# Sheet1_TRP.net
KiCad netlist of a schematic drawn in Altium Designer
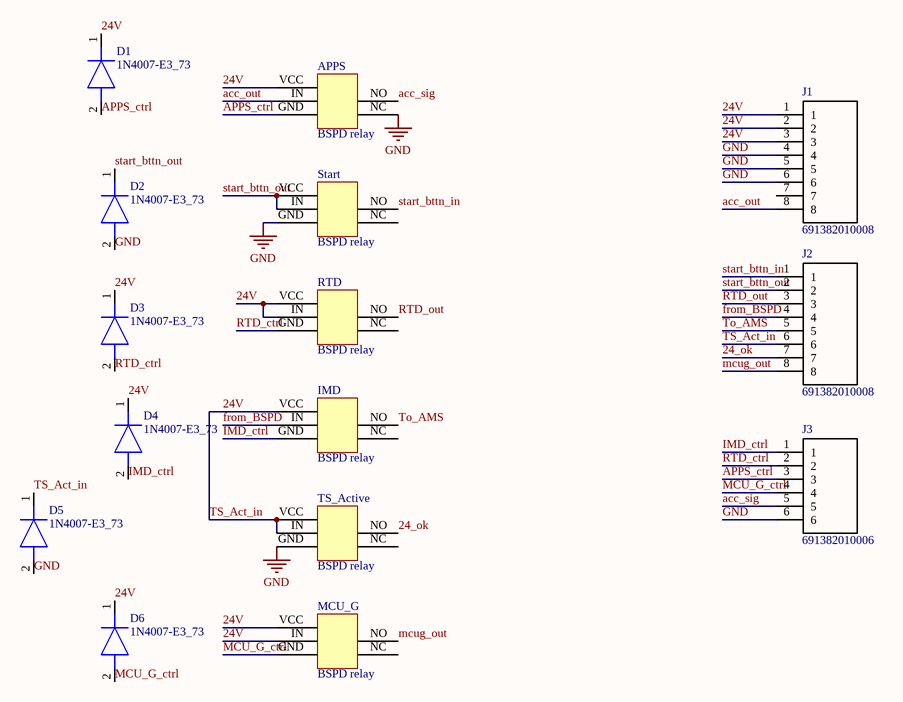
[diagram p0: Sheet1_TRP.SchDoc]

(export (version "E")
  (design (tool "Eeschema 10.0.6"))
  (components
    (comp (ref "APPS")
      (value "BSPD relay")
      (footprint "relay")
      (libsource (lib "Schlib1_TRP") (part "leone_relay"))
    )
    (comp (ref "D1")
      (value "1N4007-E3_73")
      (footprint "PcbLib1_TRP:DIOAD1405W86L465D235")
      (description "Diode")
      (fields
        (field (name "MANUFACTURER_PART_NUMBER") "1N4007-E3/73")
        (field (name "MOUSER PART NUMBER") "625-1N4007-E3/73")
      )
      (libsource (lib "*") (part "1N4007-E3_73"))
    )
    (comp (ref "D2")
      (value "1N4007-E3_73")
      (footprint "PcbLib1_TRP:DIOAD1405W86L465D235")
      (description "Diode")
      (fields
        (field (name "MANUFACTURER_PART_NUMBER") "1N4007-E3/73")
        (field (name "MOUSER PART NUMBER") "625-1N4007-E3/73")
      )
      (libsource (lib "*") (part "1N4007-E3_73"))
    )
    (comp (ref "D3")
      (value "1N4007-E3_73")
      (footprint "PcbLib1_TRP:DIOAD1405W86L465D235")
      (description "Diode")
      (fields
        (field (name "MANUFACTURER_PART_NUMBER") "1N4007-E3/73")
        (field (name "MOUSER PART NUMBER") "625-1N4007-E3/73")
      )
      (libsource (lib "*") (part "1N4007-E3_73"))
    )
    (comp (ref "D4")
      (value "1N4007-E3_73")
      (footprint "PcbLib1_TRP:DIOAD1405W86L465D235")
      (description "Diode")
      (fields
        (field (name "MANUFACTURER_PART_NUMBER") "1N4007-E3/73")
        (field (name "MOUSER PART NUMBER") "625-1N4007-E3/73")
      )
      (libsource (lib "*") (part "1N4007-E3_73"))
    )
    (comp (ref "D5")
      (value "1N4007-E3_73")
      (footprint "PcbLib1_TRP:DIOAD1405W86L465D235")
      (description "Diode")
      (fields
        (field (name "MANUFACTURER_PART_NUMBER") "1N4007-E3/73")
        (field (name "MOUSER PART NUMBER") "625-1N4007-E3/73")
      )
      (libsource (lib "*") (part "1N4007-E3_73"))
    )
    (comp (ref "D6")
      (value "1N4007-E3_73")
      (footprint "PcbLib1_TRP:DIOAD1405W86L465D235")
      (description "Diode")
      (fields
        (field (name "MANUFACTURER_PART_NUMBER") "1N4007-E3/73")
        (field (name "MOUSER PART NUMBER") "625-1N4007-E3/73")
      )
      (libsource (lib "*") (part "1N4007-E3_73"))
    )
    (comp (ref "IMD")
      (value "BSPD relay")
      (footprint "relay")
      (libsource (lib "Schlib1_TRP") (part "leone_relay"))
    )
    (comp (ref "J1")
      (value "691382010008")
      (footprint "PcbLib1_TRP:SHDRRA8W80P0X250_1X8_2200X1010X830P")
      (description "Connector")
      (fields (field (name "MOUSER PART NUMBER") "710-691382010008"))
      (libsource (lib "Schlib1_TRP") (part "691382010008"))
    )
    (comp (ref "J2")
      (value "691382010008")
      (footprint "PcbLib1_TRP:SHDRRA8W80P0X250_1X8_2200X1010X830P")
      (description "Connector")
      (fields (field (name "MOUSER PART NUMBER") "710-691382010008"))
      (libsource (lib "Schlib1_TRP") (part "691382010008"))
    )
    (comp (ref "J3")
      (value "691382010006")
      (footprint "PcbLib1_TRP:SHDRRA6W100P0X250_1X6_1700X1010X830P")
      (description "Connector")
      (fields (field (name "MOUSER PART NUMBER") "710-691382010006"))
      (libsource (lib "*") (part "691382010006"))
    )
    (comp (ref "MCU_G")
      (value "BSPD relay")
      (footprint "relay")
      (libsource (lib "Schlib1_TRP") (part "leone_relay"))
    )
    (comp (ref "RTD")
      (value "BSPD relay")
      (footprint "relay")
      (libsource (lib "Schlib1_TRP") (part "leone_relay"))
    )
    (comp (ref "Start")
      (value "BSPD relay")
      (footprint "relay")
      (libsource (lib "Schlib1_TRP") (part "leone_relay"))
    )
    (comp (ref "TS_Active")
      (value "BSPD relay")
      (footprint "relay")
      (libsource (lib "Schlib1_TRP") (part "leone_relay"))
    )
  )
  (nets
    (net (code "1") (name "/24V") (class "Default")
      (node (ref "APPS") (pin "VCC") (pintype "passive"))
      (node (ref "D1") (pin "1") (pinfunction "K_1") (pintype "passive"))
      (node (ref "D3") (pin "1") (pinfunction "K_1") (pintype "passive"))
      (node (ref "D4") (pin "1") (pinfunction "K_1") (pintype "passive"))
      (node (ref "D5") (pin "1") (pinfunction "K_1") (pintype "passive"))
      (node (ref "D6") (pin "1") (pinfunction "K_1") (pintype "passive"))
      (node (ref "IMD") (pin "VCC") (pintype "passive"))
      (node (ref "J1") (pin "1") (pinfunction "1_1") (pintype "passive"))
      (node (ref "J1") (pin "2") (pinfunction "2_2") (pintype "passive"))
      (node (ref "J1") (pin "3") (pinfunction "3_3") (pintype "passive"))
      (node (ref "J2") (pin "6") (pinfunction "6_6") (pintype "passive"))
      (node (ref "MCU_G") (pin "IN") (pintype "passive"))
      (node (ref "MCU_G") (pin "VCC") (pintype "passive"))
      (node (ref "RTD") (pin "IN") (pintype "passive"))
      (node (ref "RTD") (pin "VCC") (pintype "passive"))
      (node (ref "TS_Active") (pin "IN") (pintype "passive"))
      (node (ref "TS_Active") (pin "VCC") (pintype "passive"))
    )
    (net (code "2") (name "/24_ok") (class "Default")
      (node (ref "J2") (pin "7") (pinfunction "7_7") (pintype "passive"))
      (node (ref "TS_Active") (pin "NO") (pintype "passive"))
    )
    (net (code "3") (name "/APPS_ctrl") (class "Default")
      (node (ref "APPS") (pin "GND") (pintype "passive"))
      (node (ref "D1") (pin "2") (pinfunction "A_2") (pintype "passive"))
      (node (ref "J3") (pin "3") (pinfunction "3_3") (pintype "passive"))
    )
    (net (code "4") (name "/IMD_ctrl") (class "Default")
      (node (ref "D4") (pin "2") (pinfunction "A_2") (pintype "passive"))
      (node (ref "IMD") (pin "GND") (pintype "passive"))
      (node (ref "J3") (pin "1") (pinfunction "1_1") (pintype "passive"))
    )
    (net (code "5") (name "/MCU_G_ctrl") (class "Default")
      (node (ref "D6") (pin "2") (pinfunction "A_2") (pintype "passive"))
      (node (ref "J3") (pin "4") (pinfunction "4_4") (pintype "passive"))
      (node (ref "MCU_G") (pin "GND") (pintype "passive"))
    )
    (net (code "6") (name "/RTD_ctrl") (class "Default")
      (node (ref "D3") (pin "2") (pinfunction "A_2") (pintype "passive"))
      (node (ref "J3") (pin "2") (pinfunction "2_2") (pintype "passive"))
      (node (ref "RTD") (pin "GND") (pintype "passive"))
    )
    (net (code "7") (name "/RTD_out") (class "Default")
      (node (ref "J2") (pin "3") (pinfunction "3_3") (pintype "passive"))
      (node (ref "RTD") (pin "NO") (pintype "passive"))
    )
    (net (code "8") (name "/To_AMS") (class "Default")
      (node (ref "IMD") (pin "NO") (pintype "passive"))
      (node (ref "J2") (pin "5") (pinfunction "5_5") (pintype "passive"))
    )
    (net (code "9") (name "/acc_out") (class "Default")
      (node (ref "APPS") (pin "IN") (pintype "passive"))
      (node (ref "J1") (pin "8") (pinfunction "8_8") (pintype "passive"))
    )
    (net (code "10") (name "/acc_sig") (class "Default")
      (node (ref "APPS") (pin "NO") (pintype "passive"))
      (node (ref "J3") (pin "5") (pinfunction "5_5") (pintype "passive"))
    )
    (net (code "11") (name "/from_BSPD") (class "Default")
      (node (ref "IMD") (pin "IN") (pintype "passive"))
      (node (ref "J2") (pin "4") (pinfunction "4_4") (pintype "passive"))
    )
    (net (code "12") (name "/mcug_out") (class "Default")
      (node (ref "J2") (pin "8") (pinfunction "8_8") (pintype "passive"))
      (node (ref "MCU_G") (pin "NO") (pintype "passive"))
    )
    (net (code "13") (name "/start_bttn_in") (class "Default")
      (node (ref "J2") (pin "1") (pinfunction "1_1") (pintype "passive"))
      (node (ref "Start") (pin "NO") (pintype "passive"))
    )
    (net (code "14") (name "/start_bttn_out") (class "Default")
      (node (ref "D2") (pin "1") (pinfunction "K_1") (pintype "passive"))
      (node (ref "J2") (pin "2") (pinfunction "2_2") (pintype "passive"))
      (node (ref "Start") (pin "IN") (pintype "passive"))
      (node (ref "Start") (pin "VCC") (pintype "passive"))
    )
    (net (code "15") (name "GND") (class "Default")
      (node (ref "APPS") (pin "NC") (pintype "passive"))
      (node (ref "D2") (pin "2") (pinfunction "A_2") (pintype "passive"))
      (node (ref "D5") (pin "2") (pinfunction "A_2") (pintype "passive"))
      (node (ref "J1") (pin "4") (pinfunction "4_4") (pintype "passive"))
      (node (ref "J1") (pin "5") (pinfunction "5_5") (pintype "passive"))
      (node (ref "J1") (pin "6") (pinfunction "6_6") (pintype "passive"))
      (node (ref "J3") (pin "6") (pinfunction "6_6") (pintype "passive"))
      (node (ref "Start") (pin "GND") (pintype "passive"))
      (node (ref "TS_Active") (pin "GND") (pintype "passive"))
    )
    (net (code "16") (name "unconnected-(IMD-PadNC)") (class "Default")
      (node (ref "IMD") (pin "NC") (pintype "passive"))
    )
    (net (code "17") (name "unconnected-(J1-Pad7)") (class "Default")
      (node (ref "J1") (pin "7") (pinfunction "7_7") (pintype "passive"))
    )
    (net (code "18") (name "unconnected-(MCU_G-PadNC)") (class "Default")
      (node (ref "MCU_G") (pin "NC") (pintype "passive"))
    )
    (net (code "19") (name "unconnected-(RTD-PadNC)") (class "Default")
      (node (ref "RTD") (pin "NC") (pintype "passive"))
    )
    (net (code "20") (name "unconnected-(Start-PadNC)") (class "Default")
      (node (ref "Start") (pin "NC") (pintype "passive"))
    )
    (net (code "21") (name "unconnected-(TS_Active-PadNC)") (class "Default")
      (node (ref "TS_Active") (pin "NC") (pintype "passive"))
    )
  )
)
